# ECL_Fanout.net
KiCad netlist of a schematic drawn in Altium Designer
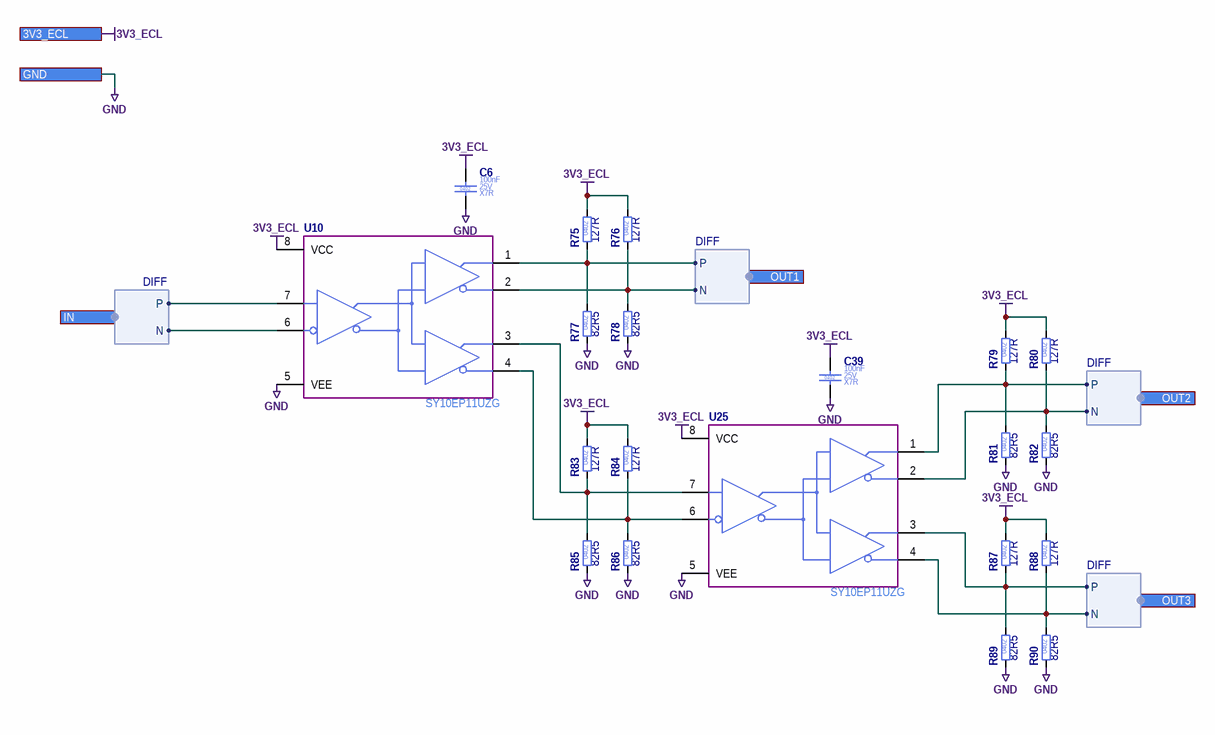
[diagram p0: ECL_Fanout.SchDoc]

(export (version "E")
  (design (tool "Eeschema 10.0.6"))
  (components
    (comp (ref "C6")
      (value "C_100NF_25V_X7R_0402_10")
      (footprint "C_0402_1005")
      (description "Ceramic Capacitor")
      (fields
        (field (name "CASE/PACKAGE") "0402")
        (field (name "VOLTAGE RATING (DC)") "25V")
        (field (name "DIELECTRIC") "X7R")
        (field (name "CAPACITANCE") "100nF")
        (field (name "TOLERANCE") "10%")
        (field (name "MANUFACTURER PART NUMBER") "EMK105B7104KV-F")
      )
      (libsource (lib "7Sigma") (part "C"))
    )
    (comp (ref "C39")
      (value "C_100NF_25V_X7R_0402_10")
      (footprint "C_0402_1005")
      (description "Ceramic Capacitor")
      (fields
        (field (name "CASE/PACKAGE") "0402")
        (field (name "VOLTAGE RATING (DC)") "25V")
        (field (name "DIELECTRIC") "X7R")
        (field (name "CAPACITANCE") "100nF")
        (field (name "TOLERANCE") "10%")
        (field (name "MANUFACTURER PART NUMBER") "EMK105B7104KV-F")
      )
      (libsource (lib "7Sigma") (part "C"))
    )
    (comp (ref "R75")
      (value "R_127R_0402_1")
      (footprint "R_0402_1005")
      (description "Thick Film Resistor")
      (fields
        (field (name "RESISTANCE") "127R")
        (field (name "CASE/PACKAGE") "0402")
        (field (name "TOLERANCE") "1%")
        (field (name "MANUFACTURER") "Yageo")
      )
      (libsource (lib "7Sigma") (part "R"))
    )
    (comp (ref "R76")
      (value "R_127R_0402_1")
      (footprint "R_0402_1005")
      (description "Thick Film Resistor")
      (fields
        (field (name "RESISTANCE") "127R")
        (field (name "CASE/PACKAGE") "0402")
        (field (name "TOLERANCE") "1%")
        (field (name "MANUFACTURER") "Yageo")
      )
      (libsource (lib "7Sigma") (part "R"))
    )
    (comp (ref "R77")
      (value "R_82R5_0402_1")
      (footprint "R_0402_1005")
      (description "Thick Film Resistor")
      (fields
        (field (name "RESISTANCE") "82R5")
        (field (name "CASE/PACKAGE") "0402")
        (field (name "TOLERANCE") "1%")
        (field (name "MANUFACTURER") "Yageo")
      )
      (libsource (lib "7Sigma") (part "R"))
    )
    (comp (ref "R78")
      (value "R_82R5_0402_1")
      (footprint "R_0402_1005")
      (description "Thick Film Resistor")
      (fields
        (field (name "RESISTANCE") "82R5")
        (field (name "CASE/PACKAGE") "0402")
        (field (name "TOLERANCE") "1%")
        (field (name "MANUFACTURER") "Yageo")
      )
      (libsource (lib "7Sigma") (part "R"))
    )
    (comp (ref "R79")
      (value "R_127R_0402_1")
      (footprint "R_0402_1005")
      (description "Thick Film Resistor")
      (fields
        (field (name "RESISTANCE") "127R")
        (field (name "CASE/PACKAGE") "0402")
        (field (name "TOLERANCE") "1%")
        (field (name "MANUFACTURER") "Yageo")
      )
      (libsource (lib "7Sigma") (part "R"))
    )
    (comp (ref "R80")
      (value "R_127R_0402_1")
      (footprint "R_0402_1005")
      (description "Thick Film Resistor")
      (fields
        (field (name "RESISTANCE") "127R")
        (field (name "CASE/PACKAGE") "0402")
        (field (name "TOLERANCE") "1%")
        (field (name "MANUFACTURER") "Yageo")
      )
      (libsource (lib "7Sigma") (part "R"))
    )
    (comp (ref "R81")
      (value "R_82R5_0402_1")
      (footprint "R_0402_1005")
      (description "Thick Film Resistor")
      (fields
        (field (name "RESISTANCE") "82R5")
        (field (name "CASE/PACKAGE") "0402")
        (field (name "TOLERANCE") "1%")
        (field (name "MANUFACTURER") "Yageo")
      )
      (libsource (lib "7Sigma") (part "R"))
    )
    (comp (ref "R82")
      (value "R_82R5_0402_1")
      (footprint "R_0402_1005")
      (description "Thick Film Resistor")
      (fields
        (field (name "RESISTANCE") "82R5")
        (field (name "CASE/PACKAGE") "0402")
        (field (name "TOLERANCE") "1%")
        (field (name "MANUFACTURER") "Yageo")
      )
      (libsource (lib "7Sigma") (part "R"))
    )
    (comp (ref "R83")
      (value "R_127R_0402_1")
      (footprint "R_0402_1005")
      (description "Thick Film Resistor")
      (fields
        (field (name "RESISTANCE") "127R")
        (field (name "CASE/PACKAGE") "0402")
        (field (name "TOLERANCE") "1%")
        (field (name "MANUFACTURER") "Yageo")
      )
      (libsource (lib "7Sigma") (part "R"))
    )
    (comp (ref "R84")
      (value "R_127R_0402_1")
      (footprint "R_0402_1005")
      (description "Thick Film Resistor")
      (fields
        (field (name "RESISTANCE") "127R")
        (field (name "CASE/PACKAGE") "0402")
        (field (name "TOLERANCE") "1%")
        (field (name "MANUFACTURER") "Yageo")
      )
      (libsource (lib "7Sigma") (part "R"))
    )
    (comp (ref "R85")
      (value "R_82R5_0402_1")
      (footprint "R_0402_1005")
      (description "Thick Film Resistor")
      (fields
        (field (name "RESISTANCE") "82R5")
        (field (name "CASE/PACKAGE") "0402")
        (field (name "TOLERANCE") "1%")
        (field (name "MANUFACTURER") "Yageo")
      )
      (libsource (lib "7Sigma") (part "R"))
    )
    (comp (ref "R86")
      (value "R_82R5_0402_1")
      (footprint "R_0402_1005")
      (description "Thick Film Resistor")
      (fields
        (field (name "RESISTANCE") "82R5")
        (field (name "CASE/PACKAGE") "0402")
        (field (name "TOLERANCE") "1%")
        (field (name "MANUFACTURER") "Yageo")
      )
      (libsource (lib "7Sigma") (part "R"))
    )
    (comp (ref "R87")
      (value "R_127R_0402_1")
      (footprint "R_0402_1005")
      (description "Thick Film Resistor")
      (fields
        (field (name "RESISTANCE") "127R")
        (field (name "CASE/PACKAGE") "0402")
        (field (name "TOLERANCE") "1%")
        (field (name "MANUFACTURER") "Yageo")
      )
      (libsource (lib "7Sigma") (part "R"))
    )
    (comp (ref "R88")
      (value "R_127R_0402_1")
      (footprint "R_0402_1005")
      (description "Thick Film Resistor")
      (fields
        (field (name "RESISTANCE") "127R")
        (field (name "CASE/PACKAGE") "0402")
        (field (name "TOLERANCE") "1%")
        (field (name "MANUFACTURER") "Yageo")
      )
      (libsource (lib "7Sigma") (part "R"))
    )
    (comp (ref "R89")
      (value "R_82R5_0402_1")
      (footprint "R_0402_1005")
      (description "Thick Film Resistor")
      (fields
        (field (name "RESISTANCE") "82R5")
        (field (name "CASE/PACKAGE") "0402")
        (field (name "TOLERANCE") "1%")
        (field (name "MANUFACTURER") "Yageo")
      )
      (libsource (lib "7Sigma") (part "R"))
    )
    (comp (ref "R90")
      (value "R_82R5_0402_1")
      (footprint "R_0402_1005")
      (description "Thick Film Resistor")
      (fields
        (field (name "RESISTANCE") "82R5")
        (field (name "CASE/PACKAGE") "0402")
        (field (name "TOLERANCE") "1%")
        (field (name "MANUFACTURER") "Yageo")
      )
      (libsource (lib "7Sigma") (part "R"))
    )
    (comp (ref "U10")
      (value "SY10EP11UZG")
      (footprint "SOIC127P600X170-8N")
      (description "1:2 PECL Fanout Buffer")
      (fields
        (field (name "MANUFACTURER") "Microchip")
        (field (name "MANUFACTURER PART NUMBER") "SY10EP11UZG")
      )
      (libsource (lib "7Sigma") (part "SY10EP11U"))
    )
    (comp (ref "U25")
      (value "SY10EP11UZG")
      (footprint "SOIC127P600X170-8N")
      (description "1:2 PECL Fanout Buffer")
      (fields
        (field (name "MANUFACTURER") "Microchip")
        (field (name "MANUFACTURER PART NUMBER") "SY10EP11UZG")
      )
      (libsource (lib "7Sigma") (part "SY10EP11U"))
    )
  )
  (nets
    (net (code "3") (name "3V3_ECL") (class "Default")
      (node (ref "C39") (pin "1") (pinfunction "1_1") (pintype "passive"))
      (node (ref "C6") (pin "1") (pinfunction "1_1") (pintype "passive"))
      (node (ref "R75") (pin "2") (pinfunction "2_2") (pintype "passive"))
      (node (ref "R76") (pin "2") (pinfunction "2_2") (pintype "passive"))
      (node (ref "R79") (pin "2") (pinfunction "2_2") (pintype "passive"))
      (node (ref "R80") (pin "2") (pinfunction "2_2") (pintype "passive"))
      (node (ref "R83") (pin "2") (pinfunction "2_2") (pintype "passive"))
      (node (ref "R84") (pin "2") (pinfunction "2_2") (pintype "passive"))
      (node (ref "R87") (pin "2") (pinfunction "2_2") (pintype "passive"))
      (node (ref "R88") (pin "2") (pinfunction "2_2") (pintype "passive"))
      (node (ref "U10") (pin "8") (pinfunction "VCC_8") (pintype "passive"))
      (node (ref "U25") (pin "8") (pinfunction "VCC_8") (pintype "passive"))
    )
    (net (code "4") (name "GND") (class "Default")
      (node (ref "C39") (pin "2") (pinfunction "2_2") (pintype "passive"))
      (node (ref "C6") (pin "2") (pinfunction "2_2") (pintype "passive"))
      (node (ref "R77") (pin "1") (pinfunction "1_1") (pintype "passive"))
      (node (ref "R78") (pin "1") (pinfunction "1_1") (pintype "passive"))
      (node (ref "R81") (pin "1") (pinfunction "1_1") (pintype "passive"))
      (node (ref "R82") (pin "1") (pinfunction "1_1") (pintype "passive"))
      (node (ref "R85") (pin "1") (pinfunction "1_1") (pintype "passive"))
      (node (ref "R86") (pin "1") (pinfunction "1_1") (pintype "passive"))
      (node (ref "R89") (pin "1") (pinfunction "1_1") (pintype "passive"))
      (node (ref "R90") (pin "1") (pinfunction "1_1") (pintype "passive"))
      (node (ref "U10") (pin "5") (pinfunction "VEE_5") (pintype "passive"))
      (node (ref "U25") (pin "5") (pinfunction "VEE_5") (pintype "passive"))
    )
    (net (code "5") (name "Net-(R83-Pad1)") (class "Default")
      (node (ref "R83") (pin "1") (pinfunction "1_1") (pintype "passive"))
      (node (ref "R85") (pin "2") (pinfunction "2_2") (pintype "passive"))
      (node (ref "U10") (pin "3") (pinfunction "Q1_3") (pintype "passive"))
      (node (ref "U25") (pin "7") (pinfunction "D_7") (pintype "passive"))
    )
    (net (code "6") (name "Net-(R84-Pad1)") (class "Default")
      (node (ref "R84") (pin "1") (pinfunction "1_1") (pintype "passive"))
      (node (ref "R86") (pin "2") (pinfunction "2_2") (pintype "passive"))
      (node (ref "U10") (pin "4") (pinfunction "Q1_4") (pintype "passive"))
      (node (ref "U25") (pin "6") (pinfunction "D_6") (pintype "passive"))
    )
    (net (code "7") (name "Net-(R87-Pad1)") (class "Default")
      (node (ref "R87") (pin "1") (pinfunction "1_1") (pintype "passive"))
      (node (ref "R89") (pin "2") (pinfunction "2_2") (pintype "passive"))
      (node (ref "U25") (pin "3") (pinfunction "Q1_3") (pintype "passive"))
    )
    (net (code "8") (name "Net-(R88-Pad1)") (class "Default")
      (node (ref "R88") (pin "1") (pinfunction "1_1") (pintype "passive"))
      (node (ref "R90") (pin "2") (pinfunction "2_2") (pintype "passive"))
      (node (ref "U25") (pin "4") (pinfunction "Q1_4") (pintype "passive"))
    )
    (net (code "9") (name "Net-(U10-Q0)") (class "Default")
      (node (ref "R75") (pin "1") (pinfunction "1_1") (pintype "passive"))
      (node (ref "R77") (pin "2") (pinfunction "2_2") (pintype "passive"))
      (node (ref "U10") (pin "1") (pinfunction "Q0_1") (pintype "passive"))
    )
    (net (code "10") (name "Net-(U10-{slash}Q0)") (class "Default")
      (node (ref "R76") (pin "1") (pinfunction "1_1") (pintype "passive"))
      (node (ref "R78") (pin "2") (pinfunction "2_2") (pintype "passive"))
      (node (ref "U10") (pin "2") (pinfunction "/Q0_2") (pintype "passive"))
    )
    (net (code "11") (name "Net-(U25-Q0)") (class "Default")
      (node (ref "R79") (pin "1") (pinfunction "1_1") (pintype "passive"))
      (node (ref "R81") (pin "2") (pinfunction "2_2") (pintype "passive"))
      (node (ref "U25") (pin "1") (pinfunction "Q0_1") (pintype "passive"))
    )
    (net (code "12") (name "Net-(U25-{slash}Q0)") (class "Default")
      (node (ref "R80") (pin "1") (pinfunction "1_1") (pintype "passive"))
      (node (ref "R82") (pin "2") (pinfunction "2_2") (pintype "passive"))
      (node (ref "U25") (pin "2") (pinfunction "/Q0_2") (pintype "passive"))
    )
    (net (code "13") (name "unconnected-(U10-D-Pad6)") (class "Default")
      (node (ref "U10") (pin "6") (pinfunction "D_6") (pintype "passive"))
    )
    (net (code "14") (name "unconnected-(U10-D-Pad7)") (class "Default")
      (node (ref "U10") (pin "7") (pinfunction "D_7") (pintype "passive"))
    )
  )
)
